# DRV8350R_Schematic.net
KiCad netlist of a schematic drawn in Altium Designer
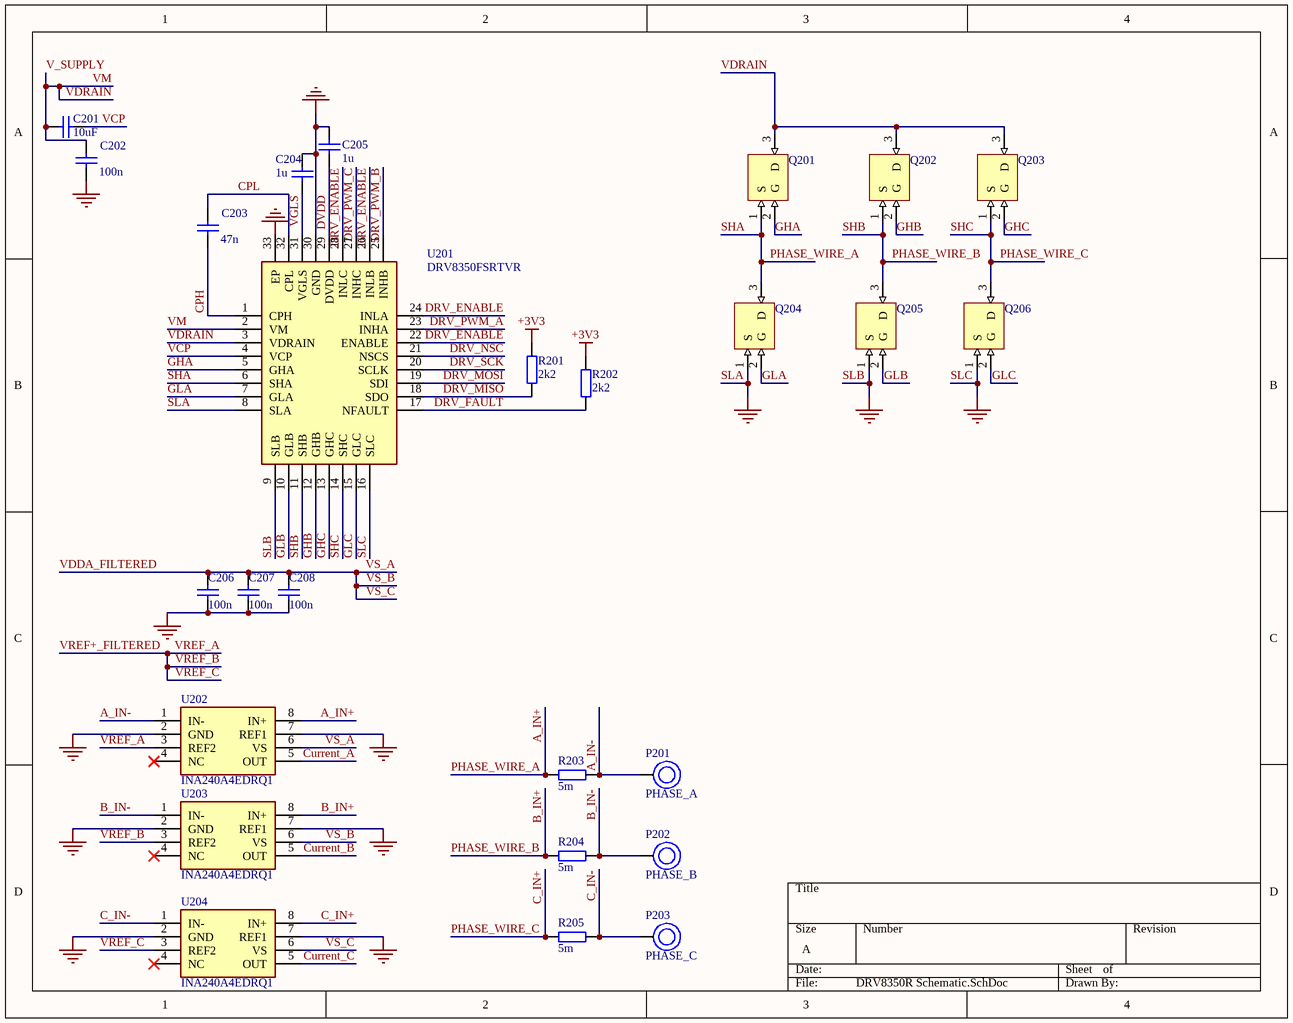
[diagram p0: DRV8350R Schematic.SchDoc]

(export (version "E")
  (design (tool "Eeschema 10.0.6"))
  (components
    (comp (ref "C201")
      (value "10uF")
      (footprint "FootprintLib:CAPC1608X90N")
      (description "Capacitor")
      (fields
        (field (name "MANUFACTURER_PART_NUMBER") "CL05B104KO5NNNC")
        (field (name "MOUSER PART NUMBER") "187-CL05B104KO5NNNC")
      )
      (libsource (lib "SymbolLib") (part "CAP_0805_50V"))
    )
    (comp (ref "C202")
      (value "100n")
      (footprint "FootprintLib:CAPC1608X90N")
      (description "Capacitor")
      (fields
        (field (name "MANUFACTURER_PART_NUMBER") "CL05B104KO5NNNC")
        (field (name "MOUSER PART NUMBER") "187-CL05B104KO5NNNC")
      )
      (libsource (lib "SymbolLib") (part "CAP_0603_100V"))
    )
    (comp (ref "C203")
      (value "47n")
      (footprint "FootprintLib:CAPC1005X55N")
      (description "Capacitor")
      (fields
        (field (name "MANUFACTURER_PART_NUMBER") "CL05B104KO5NNNC")
        (field (name "MOUSER PART NUMBER") "187-CL05B104KO5NNNC")
      )
      (libsource (lib "SymbolLib") (part "CAP_0402_50V"))
    )
    (comp (ref "C204")
      (value "1u")
      (footprint "FootprintLib:CAPC1005X55N")
      (description "Capacitor")
      (fields
        (field (name "MANUFACTURER_PART_NUMBER") "CL05B104KO5NNNC")
        (field (name "MOUSER PART NUMBER") "187-CL05B104KO5NNNC")
      )
      (libsource (lib "SymbolLib") (part "CAP_0402_50V"))
    )
    (comp (ref "C205")
      (value "1u")
      (footprint "FootprintLib:CAPC1005X55N")
      (description "Capacitor")
      (fields
        (field (name "MANUFACTURER_PART_NUMBER") "CL05B104KO5NNNC")
        (field (name "MOUSER PART NUMBER") "187-CL05B104KO5NNNC")
      )
      (libsource (lib "SymbolLib") (part "CAP_0402_50V"))
    )
    (comp (ref "C206")
      (value "100n")
      (footprint "CAPC1050X55X23ML05T13")
      (description "Chip Capacitor, 100 nF, +/- 10%, 16 V, -55 to 125 degC, 0402 (1005 Metric), RoHS, Tape and Reel")
      (fields (field (name "MANUFACTURER") "Samsung Electro-Mechanics"))
      (libsource (lib "Altium Content Vault") (part "CAP-NP-2"))
    )
    (comp (ref "C207")
      (value "100n")
      (footprint "CAPC1050X55X23ML05T13")
      (description "Chip Capacitor, 100 nF, +/- 10%, 16 V, -55 to 125 degC, 0402 (1005 Metric), RoHS, Tape and Reel")
      (fields (field (name "MANUFACTURER") "Samsung Electro-Mechanics"))
      (libsource (lib "Altium Content Vault") (part "CAP-NP-2"))
    )
    (comp (ref "C208")
      (value "100n")
      (footprint "CAPC1050X55X23ML05T13")
      (description "Chip Capacitor, 100 nF, +/- 10%, 16 V, -55 to 125 degC, 0402 (1005 Metric), RoHS, Tape and Reel")
      (fields (field (name "MANUFACTURER") "Samsung Electro-Mechanics"))
      (libsource (lib "Altium Content Vault") (part "CAP-NP-2"))
    )
    (comp (ref "P201")
      (value "PHASE_A")
      (footprint "PAD_HOLE")
      (libsource (lib "SymbolLib") (part "3MM_PAD"))
    )
    (comp (ref "P202")
      (value "PHASE_B")
      (footprint "PAD_HOLE")
      (libsource (lib "SymbolLib") (part "3MM_PAD"))
    )
    (comp (ref "P203")
      (value "PHASE_C")
      (footprint "PAD_HOLE")
      (libsource (lib "SymbolLib") (part "3MM_PAD"))
    )
    (comp (ref "Q201")
      (value "NTTFS3D7N06HLTWG")
      (footprint "PQFN-8")
      (libsource (lib "SymbolLib") (part "NTTFS3D7N06HLTWG"))
    )
    (comp (ref "Q202")
      (value "NTTFS3D7N06HLTWG")
      (footprint "PQFN-8")
      (libsource (lib "SymbolLib") (part "NTTFS3D7N06HLTWG"))
    )
    (comp (ref "Q203")
      (value "NTTFS3D7N06HLTWG")
      (footprint "PQFN-8")
      (libsource (lib "SymbolLib") (part "NTTFS3D7N06HLTWG"))
    )
    (comp (ref "Q204")
      (value "NTTFS3D7N06HLTWG")
      (footprint "PQFN-8")
      (libsource (lib "SymbolLib") (part "NTTFS3D7N06HLTWG"))
    )
    (comp (ref "Q205")
      (value "NTTFS3D7N06HLTWG")
      (footprint "PQFN-8")
      (libsource (lib "SymbolLib") (part "NTTFS3D7N06HLTWG"))
    )
    (comp (ref "Q206")
      (value "NTTFS3D7N06HLTWG")
      (footprint "PQFN-8")
      (libsource (lib "SymbolLib") (part "NTTFS3D7N06HLTWG"))
    )
    (comp (ref "R201")
      (value "2k2")
      (footprint "RESC1608X55N")
      (libsource (lib "SymbolLib") (part "RES_0603"))
    )
    (comp (ref "R202")
      (value "2k2")
      (footprint "RESC1608X55N")
      (libsource (lib "SymbolLib") (part "RES_0603"))
    )
    (comp (ref "R203")
      (value "5m")
      (footprint "RESC3216X80N")
      (libsource (lib "SymbolLib") (part "RES_1206"))
    )
    (comp (ref "R204")
      (value "5m")
      (footprint "RESC3216X80N")
      (libsource (lib "SymbolLib") (part "RES_1206"))
    )
    (comp (ref "R205")
      (value "5m")
      (footprint "RESC3216X80N")
      (libsource (lib "SymbolLib") (part "RES_1206"))
    )
    (comp (ref "U201")
      (value "DRV8350FSRTVR")
      (footprint "WQFN-N32-THM")
      (libsource (lib "SymbolLib") (part "DRV8350FSRTVR"))
    )
    (comp (ref "U202")
      (value "INA240A4EDRQ1")
      (footprint "SamacSys:SOIC127P600X175-8N")
      (description "Integrated Circuit")
      (fields (field (name "MOUSER PART NUMBER") "595-INA240A4EDRQ1"))
      (libsource (lib "*") (part "INA240A4EDRQ1"))
    )
    (comp (ref "U203")
      (value "INA240A4EDRQ1")
      (footprint "SamacSys:SOIC127P600X175-8N")
      (description "Integrated Circuit")
      (fields (field (name "MOUSER PART NUMBER") "595-INA240A4EDRQ1"))
      (libsource (lib "*") (part "INA240A4EDRQ1"))
    )
    (comp (ref "U204")
      (value "INA240A4EDRQ1")
      (footprint "SamacSys:SOIC127P600X175-8N")
      (description "Integrated Circuit")
      (fields (field (name "MOUSER PART NUMBER") "595-INA240A4EDRQ1"))
      (libsource (lib "*") (part "INA240A4EDRQ1"))
    )
  )
  (nets
    (net (code "1") (name "+3V3") (class "Default")
      (node (ref "R201") (pin "2") (pinfunction "2_2") (pintype "passive"))
      (node (ref "R202") (pin "2") (pinfunction "2_2") (pintype "passive"))
    )
    (net (code "2") (name "/A_IN+") (class "Default")
      (node (ref "Q201") (pin "1") (pinfunction "S_1") (pintype "input"))
      (node (ref "Q204") (pin "3") (pinfunction "D_3") (pintype "input"))
      (node (ref "R203") (pin "1") (pinfunction "1_1") (pintype "passive"))
      (node (ref "U201") (pin "6") (pinfunction "SHA_6") (pintype "passive"))
      (node (ref "U202") (pin "8") (pinfunction "IN+_8") (pintype "passive"))
    )
    (net (code "3") (name "/A_IN-") (class "Default")
      (node (ref "P201") (pin "1") (pinfunction "1_1") (pintype "passive"))
      (node (ref "R203") (pin "2") (pinfunction "2_2") (pintype "passive"))
      (node (ref "U202") (pin "1") (pinfunction "IN-_1") (pintype "passive"))
    )
    (net (code "4") (name "/B_IN+") (class "Default")
      (node (ref "Q202") (pin "1") (pinfunction "S_1") (pintype "input"))
      (node (ref "Q205") (pin "3") (pinfunction "D_3") (pintype "input"))
      (node (ref "R204") (pin "1") (pinfunction "1_1") (pintype "passive"))
      (node (ref "U201") (pin "11") (pinfunction "SHB_11") (pintype "passive"))
      (node (ref "U203") (pin "8") (pinfunction "IN+_8") (pintype "passive"))
    )
    (net (code "5") (name "/B_IN-") (class "Default")
      (node (ref "P202") (pin "1") (pinfunction "1_1") (pintype "passive"))
      (node (ref "R204") (pin "2") (pinfunction "2_2") (pintype "passive"))
      (node (ref "U203") (pin "1") (pinfunction "IN-_1") (pintype "passive"))
    )
    (net (code "6") (name "/CPH") (class "Default")
      (node (ref "C203") (pin "2") (pinfunction "2_2") (pintype "passive"))
      (node (ref "U201") (pin "1") (pinfunction "CPH_1") (pintype "passive"))
    )
    (net (code "7") (name "/CPL") (class "Default")
      (node (ref "C203") (pin "1") (pinfunction "1_1") (pintype "passive"))
      (node (ref "U201") (pin "32") (pinfunction "CPL_32") (pintype "passive"))
    )
    (net (code "8") (name "/C_IN+") (class "Default")
      (node (ref "Q203") (pin "1") (pinfunction "S_1") (pintype "input"))
      (node (ref "Q206") (pin "3") (pinfunction "D_3") (pintype "input"))
      (node (ref "R205") (pin "1") (pinfunction "1_1") (pintype "passive"))
      (node (ref "U201") (pin "14") (pinfunction "SHC_14") (pintype "passive"))
      (node (ref "U204") (pin "8") (pinfunction "IN+_8") (pintype "passive"))
    )
    (net (code "9") (name "/C_IN-") (class "Default")
      (node (ref "P203") (pin "1") (pinfunction "1_1") (pintype "passive"))
      (node (ref "R205") (pin "2") (pinfunction "2_2") (pintype "passive"))
      (node (ref "U204") (pin "1") (pinfunction "IN-_1") (pintype "passive"))
    )
    (net (code "10") (name "/Current_A") (class "Default")
      (node (ref "U202") (pin "5") (pinfunction "OUT_5") (pintype "passive"))
    )
    (net (code "11") (name "/Current_B") (class "Default")
      (node (ref "U203") (pin "5") (pinfunction "OUT_5") (pintype "passive"))
    )
    (net (code "12") (name "/Current_C") (class "Default")
      (node (ref "U204") (pin "5") (pinfunction "OUT_5") (pintype "passive"))
    )
    (net (code "13") (name "/DRV_ENABLE") (class "Default")
      (node (ref "U201") (pin "22") (pinfunction "ENABLE_22") (pintype "passive"))
      (node (ref "U201") (pin "24") (pinfunction "INLA_24") (pintype "passive"))
      (node (ref "U201") (pin "26") (pinfunction "INLB_26") (pintype "passive"))
      (node (ref "U201") (pin "28") (pinfunction "INLC_28") (pintype "passive"))
    )
    (net (code "14") (name "/DRV_FAULT") (class "Default")
      (node (ref "R202") (pin "1") (pinfunction "1_1") (pintype "passive"))
      (node (ref "U201") (pin "17") (pinfunction "NFAULT_17") (pintype "passive"))
    )
    (net (code "15") (name "/DRV_MISO") (class "Default")
      (node (ref "R201") (pin "1") (pinfunction "1_1") (pintype "passive"))
      (node (ref "U201") (pin "18") (pinfunction "SDO_18") (pintype "passive"))
    )
    (net (code "16") (name "/DRV_MOSI") (class "Default")
      (node (ref "U201") (pin "19") (pinfunction "SDI_19") (pintype "passive"))
    )
    (net (code "17") (name "/DRV_NSC") (class "Default")
      (node (ref "U201") (pin "21") (pinfunction "NSCS_21") (pintype "passive"))
    )
    (net (code "18") (name "/DRV_PWM_A") (class "Default")
      (node (ref "U201") (pin "23") (pinfunction "INHA_23") (pintype "passive"))
    )
    (net (code "19") (name "/DRV_PWM_B") (class "Default")
      (node (ref "U201") (pin "25") (pinfunction "INHB_25") (pintype "passive"))
    )
    (net (code "20") (name "/DRV_PWM_C") (class "Default")
      (node (ref "U201") (pin "27") (pinfunction "INHC_27") (pintype "passive"))
    )
    (net (code "21") (name "/DRV_SCK") (class "Default")
      (node (ref "U201") (pin "20") (pinfunction "SCLK_20") (pintype "passive"))
    )
    (net (code "22") (name "/DVDD") (class "Default")
      (node (ref "C205") (pin "2") (pinfunction "2_2") (pintype "passive"))
      (node (ref "U201") (pin "29") (pinfunction "DVDD_29") (pintype "passive"))
    )
    (net (code "23") (name "/GHA") (class "Default")
      (node (ref "Q201") (pin "2") (pinfunction "G_2") (pintype "input"))
      (node (ref "U201") (pin "5") (pinfunction "GHA_5") (pintype "passive"))
    )
    (net (code "24") (name "/GHB") (class "Default")
      (node (ref "Q202") (pin "2") (pinfunction "G_2") (pintype "input"))
      (node (ref "U201") (pin "12") (pinfunction "GHB_12") (pintype "passive"))
    )
    (net (code "25") (name "/GHC") (class "Default")
      (node (ref "Q203") (pin "2") (pinfunction "G_2") (pintype "input"))
      (node (ref "U201") (pin "13") (pinfunction "GHC_13") (pintype "passive"))
    )
    (net (code "26") (name "/GLA") (class "Default")
      (node (ref "Q204") (pin "2") (pinfunction "G_2") (pintype "input"))
      (node (ref "U201") (pin "7") (pinfunction "GLA_7") (pintype "passive"))
    )
    (net (code "27") (name "/GLB") (class "Default")
      (node (ref "Q205") (pin "2") (pinfunction "G_2") (pintype "input"))
      (node (ref "U201") (pin "10") (pinfunction "GLB_10") (pintype "passive"))
    )
    (net (code "28") (name "/GLC") (class "Default")
      (node (ref "Q206") (pin "2") (pinfunction "G_2") (pintype "input"))
      (node (ref "U201") (pin "15") (pinfunction "GLC_15") (pintype "passive"))
    )
    (net (code "29") (name "/VCP") (class "Default")
      (node (ref "C201") (pin "2") (pinfunction "2_2") (pintype "passive"))
      (node (ref "U201") (pin "4") (pinfunction "VCP_4") (pintype "passive"))
    )
    (net (code "30") (name "/VDDA_FILTERED") (class "Default")
      (node (ref "C206") (pin "2") (pinfunction "2_2") (pintype "passive"))
      (node (ref "C207") (pin "2") (pinfunction "2_2") (pintype "passive"))
      (node (ref "C208") (pin "2") (pinfunction "2_2") (pintype "passive"))
      (node (ref "U202") (pin "6") (pinfunction "VS_6") (pintype "passive"))
      (node (ref "U203") (pin "6") (pinfunction "VS_6") (pintype "passive"))
      (node (ref "U204") (pin "6") (pinfunction "VS_6") (pintype "passive"))
    )
    (net (code "31") (name "/VDRAIN") (class "Default")
      (node (ref "C201") (pin "1") (pinfunction "1_1") (pintype "passive"))
      (node (ref "C202") (pin "2") (pinfunction "2_2") (pintype "passive"))
      (node (ref "Q201") (pin "3") (pinfunction "D_3") (pintype "input"))
      (node (ref "Q202") (pin "3") (pinfunction "D_3") (pintype "input"))
      (node (ref "Q203") (pin "3") (pinfunction "D_3") (pintype "input"))
      (node (ref "U201") (pin "2") (pinfunction "VM_2") (pintype "passive"))
      (node (ref "U201") (pin "3") (pinfunction "VDRAIN_3") (pintype "passive"))
    )
    (net (code "32") (name "/VGLS") (class "Default")
      (node (ref "C204") (pin "1") (pinfunction "1_1") (pintype "passive"))
      (node (ref "U201") (pin "31") (pinfunction "VGLS_31") (pintype "passive"))
    )
    (net (code "33") (name "/VREF+_FILTERED") (class "Default")
      (node (ref "U202") (pin "3") (pinfunction "REF2_3") (pintype "passive"))
      (node (ref "U203") (pin "3") (pinfunction "REF2_3") (pintype "passive"))
      (node (ref "U204") (pin "3") (pinfunction "REF2_3") (pintype "passive"))
    )
    (net (code "34") (name "GND") (class "Default")
      (node (ref "C202") (pin "1") (pinfunction "1_1") (pintype "passive"))
      (node (ref "C204") (pin "2") (pinfunction "2_2") (pintype "passive"))
      (node (ref "C205") (pin "1") (pinfunction "1_1") (pintype "passive"))
      (node (ref "C206") (pin "1") (pinfunction "1_1") (pintype "passive"))
      (node (ref "C207") (pin "1") (pinfunction "1_1") (pintype "passive"))
      (node (ref "C208") (pin "1") (pinfunction "1_1") (pintype "passive"))
      (node (ref "Q204") (pin "1") (pinfunction "S_1") (pintype "input"))
      (node (ref "Q205") (pin "1") (pinfunction "S_1") (pintype "input"))
      (node (ref "Q206") (pin "1") (pinfunction "S_1") (pintype "input"))
      (node (ref "U201") (pin "16") (pinfunction "SLC_16") (pintype "passive"))
      (node (ref "U201") (pin "30") (pinfunction "GND_30") (pintype "passive"))
      (node (ref "U201") (pin "33") (pinfunction "EP_33") (pintype "passive"))
      (node (ref "U201") (pin "8") (pinfunction "SLA_8") (pintype "passive"))
      (node (ref "U201") (pin "9") (pinfunction "SLB_9") (pintype "passive"))
      (node (ref "U202") (pin "2") (pinfunction "GND_2") (pintype "passive"))
      (node (ref "U202") (pin "7") (pinfunction "REF1_7") (pintype "passive"))
      (node (ref "U203") (pin "2") (pinfunction "GND_2") (pintype "passive"))
      (node (ref "U203") (pin "7") (pinfunction "REF1_7") (pintype "passive"))
      (node (ref "U204") (pin "2") (pinfunction "GND_2") (pintype "passive"))
      (node (ref "U204") (pin "7") (pinfunction "REF1_7") (pintype "passive"))
    )
    (net (code "35") (name "unconnected-(U202-NC-Pad4)") (class "Default")
      (node (ref "U202") (pin "4") (pinfunction "NC_4") (pintype "passive+no_connect"))
    )
    (net (code "36") (name "unconnected-(U203-NC-Pad4)") (class "Default")
      (node (ref "U203") (pin "4") (pinfunction "NC_4") (pintype "passive+no_connect"))
    )
    (net (code "37") (name "unconnected-(U204-NC-Pad4)") (class "Default")
      (node (ref "U204") (pin "4") (pinfunction "NC_4") (pintype "passive+no_connect"))
    )
  )
)
